# vca2.net
KiCad netlist of a schematic drawn in EAGLE
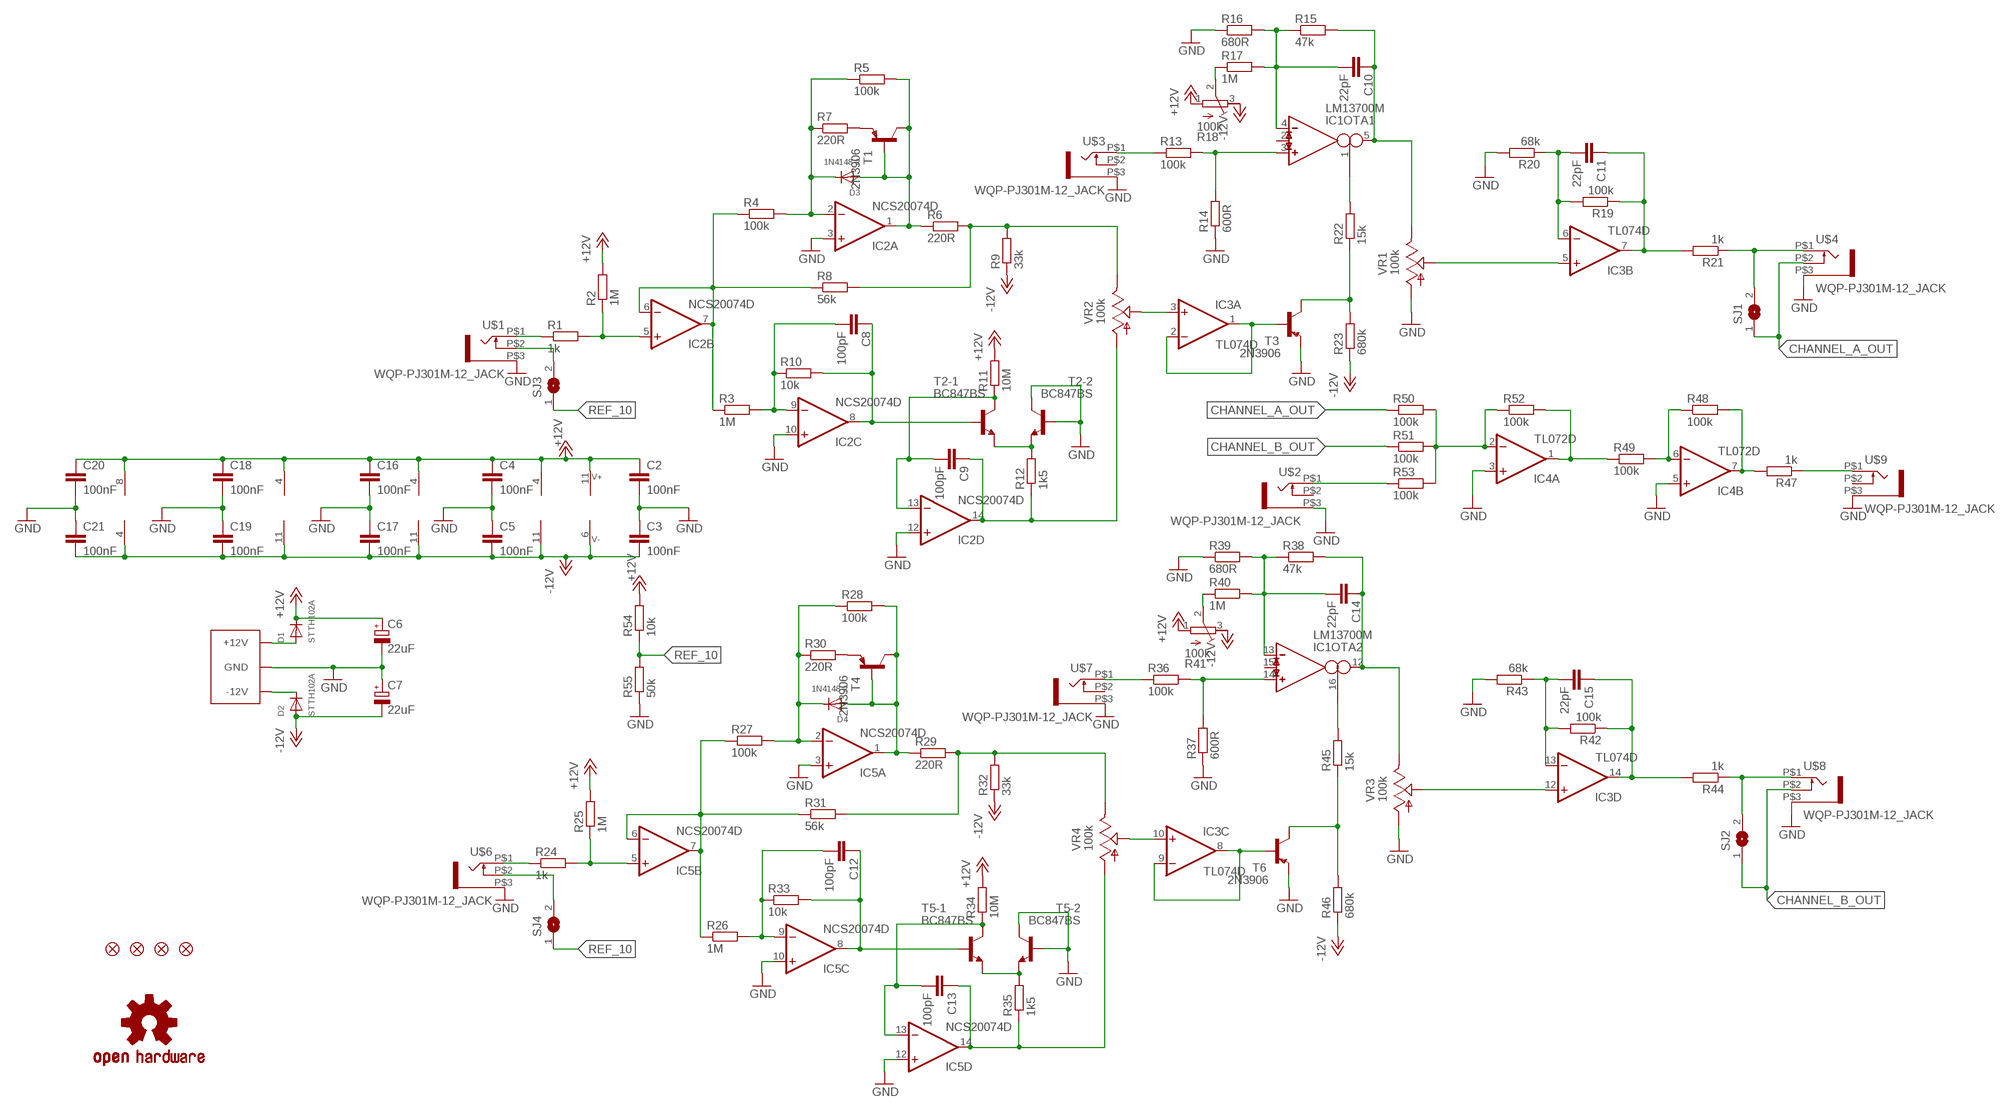
[diagram p0: schematic, sheet 1]

(export (version "E")
  (design (tool "Eeschema 10.0.6"))
  (components
    (comp (ref "C1")
      (value "EURO_POWER_LOCKFAT-LOCK")
      (footprint "eagle-import:EURO_PWR_HEADER_LOCK")
      (libsource (lib "eagle-import") (part "EURO_POWER_LOCKFAT-LOCK"))
    )
    (comp (ref "C2")
      (value "100nF")
      (footprint "eagle-import:C0603")
      (libsource (lib "eagle-import") (part "C-EUC0603"))
    )
    (comp (ref "C3")
      (value "100nF")
      (footprint "eagle-import:C0603")
      (libsource (lib "eagle-import") (part "C-EUC0603"))
    )
    (comp (ref "C4")
      (value "100nF")
      (footprint "eagle-import:C0603")
      (libsource (lib "eagle-import") (part "C-EUC0603"))
    )
    (comp (ref "C5")
      (value "100nF")
      (footprint "eagle-import:C0603")
      (libsource (lib "eagle-import") (part "C-EUC0603"))
    )
    (comp (ref "C6")
      (value "22uF")
      (footprint "eagle-import:PANASONIC_C")
      (libsource (lib "eagle-import") (part "CPOL-EUC"))
    )
    (comp (ref "C7")
      (value "22uF")
      (footprint "eagle-import:PANASONIC_C")
      (libsource (lib "eagle-import") (part "CPOL-EUC"))
    )
    (comp (ref "C8")
      (value "100pF")
      (footprint "eagle-import:C0603")
      (libsource (lib "eagle-import") (part "C-EUC0603"))
    )
    (comp (ref "C9")
      (value "100pF")
      (footprint "eagle-import:C0603")
      (libsource (lib "eagle-import") (part "C-EUC0603"))
    )
    (comp (ref "C10")
      (value "22pF")
      (footprint "eagle-import:C0603")
      (libsource (lib "eagle-import") (part "C-EUC0603"))
    )
    (comp (ref "C11")
      (value "22pF")
      (footprint "eagle-import:C0603")
      (libsource (lib "eagle-import") (part "C-EUC0603"))
    )
    (comp (ref "C12")
      (value "100pF")
      (footprint "eagle-import:C0603")
      (libsource (lib "eagle-import") (part "C-EUC0603"))
    )
    (comp (ref "C13")
      (value "100pF")
      (footprint "eagle-import:C0603")
      (libsource (lib "eagle-import") (part "C-EUC0603"))
    )
    (comp (ref "C14")
      (value "22pF")
      (footprint "eagle-import:C0603")
      (libsource (lib "eagle-import") (part "C-EUC0603"))
    )
    (comp (ref "C15")
      (value "22pF")
      (footprint "eagle-import:C0603")
      (libsource (lib "eagle-import") (part "C-EUC0603"))
    )
    (comp (ref "C16")
      (value "100nF")
      (footprint "eagle-import:C0603")
      (libsource (lib "eagle-import") (part "C-EUC0603"))
    )
    (comp (ref "C17")
      (value "100nF")
      (footprint "eagle-import:C0603")
      (libsource (lib "eagle-import") (part "C-EUC0603"))
    )
    (comp (ref "C18")
      (value "100nF")
      (footprint "eagle-import:C0603")
      (libsource (lib "eagle-import") (part "C-EUC0603"))
    )
    (comp (ref "C19")
      (value "100nF")
      (footprint "eagle-import:C0603")
      (libsource (lib "eagle-import") (part "C-EUC0603"))
    )
    (comp (ref "C20")
      (value "100nF")
      (footprint "eagle-import:C0603")
      (libsource (lib "eagle-import") (part "C-EUC0603"))
    )
    (comp (ref "C21")
      (value "100nF")
      (footprint "eagle-import:C0603")
      (libsource (lib "eagle-import") (part "C-EUC0603"))
    )
    (comp (ref "D1")
      (value "STTH102A")
      (footprint "eagle-import:SMADIODE")
      (libsource (lib "eagle-import") (part "DIODESMA"))
    )
    (comp (ref "D2")
      (value "STTH102A")
      (footprint "eagle-import:SMADIODE")
      (libsource (lib "eagle-import") (part "DIODESMA"))
    )
    (comp (ref "D3")
      (value "1N4148-2")
      (footprint "eagle-import:SOD-123")
      (libsource (lib "eagle-import") (part "DIODESOD-123"))
    )
    (comp (ref "D4")
      (value "1N4148-2")
      (footprint "eagle-import:SOD-123")
      (libsource (lib "eagle-import") (part "DIODESOD-123"))
    )
    (comp (ref "FD1")
      (value "FIDUCIAL1X2")
      (footprint "eagle-import:FIDUCIAL-1X2")
      (libsource (lib "eagle-import") (part "FIDUCIAL1X2"))
    )
    (comp (ref "FD2")
      (value "FIDUCIAL1X2")
      (footprint "eagle-import:FIDUCIAL-1X2")
      (libsource (lib "eagle-import") (part "FIDUCIAL1X2"))
    )
    (comp (ref "FD3")
      (value "FIDUCIAL1X2")
      (footprint "eagle-import:FIDUCIAL-1X2")
      (libsource (lib "eagle-import") (part "FIDUCIAL1X2"))
    )
    (comp (ref "FD4")
      (value "FIDUCIAL1X2")
      (footprint "eagle-import:FIDUCIAL-1X2")
      (libsource (lib "eagle-import") (part "FIDUCIAL1X2"))
    )
    (comp (ref "IC1")
      (value "LM13700M")
      (footprint "eagle-import:SO16")
      (libsource (lib "eagle-import") (part "LM13700M"))
    )
    (comp (ref "IC2")
      (value "NCS20074D")
      (footprint "eagle-import:SO14")
      (libsource (lib "eagle-import") (part "NCS20074D"))
    )
    (comp (ref "IC3")
      (value "TL074D")
      (footprint "eagle-import:SO14")
      (libsource (lib "eagle-import") (part "TL074D"))
    )
    (comp (ref "IC4")
      (value "TL072D")
      (footprint "eagle-import:SO08")
      (libsource (lib "eagle-import") (part "TL072D"))
    )
    (comp (ref "IC5")
      (value "NCS20074D")
      (footprint "eagle-import:SO14")
      (libsource (lib "eagle-import") (part "NCS20074D"))
    )
    (comp (ref "LOGO1")
      (value "OSHW-LOGOM")
      (footprint "eagle-import:OSHW-LOGO-M")
      (libsource (lib "eagle-import") (part "OSHW-LOGOM"))
    )
    (comp (ref "R1")
      (value "1k")
      (footprint "eagle-import:R0603")
      (libsource (lib "eagle-import") (part "R-EU_R0603"))
    )
    (comp (ref "R2")
      (value "1M")
      (footprint "eagle-import:R0603")
      (libsource (lib "eagle-import") (part "R-EU_R0603"))
    )
    (comp (ref "R3")
      (value "1M")
      (footprint "eagle-import:R0603")
      (libsource (lib "eagle-import") (part "R-EU_R0603"))
    )
    (comp (ref "R4")
      (value "100k")
      (footprint "eagle-import:R0603")
      (libsource (lib "eagle-import") (part "R-EU_R0603"))
    )
    (comp (ref "R5")
      (value "100k")
      (footprint "eagle-import:R0603")
      (libsource (lib "eagle-import") (part "R-EU_R0603"))
    )
    (comp (ref "R6")
      (value "220R")
      (footprint "eagle-import:R0603")
      (libsource (lib "eagle-import") (part "R-EU_R0603"))
    )
    (comp (ref "R7")
      (value "220R")
      (footprint "eagle-import:R0603")
      (libsource (lib "eagle-import") (part "R-EU_R0603"))
    )
    (comp (ref "R8")
      (value "56k")
      (footprint "eagle-import:R0603")
      (libsource (lib "eagle-import") (part "R-EU_R0603"))
    )
    (comp (ref "R9")
      (value "33k")
      (footprint "eagle-import:R0603")
      (libsource (lib "eagle-import") (part "R-EU_R0603"))
    )
    (comp (ref "R10")
      (value "10k")
      (footprint "eagle-import:R0603")
      (libsource (lib "eagle-import") (part "R-EU_R0603"))
    )
    (comp (ref "R11")
      (value "10M")
      (footprint "eagle-import:R0603")
      (libsource (lib "eagle-import") (part "R-EU_R0603"))
    )
    (comp (ref "R12")
      (value "1k5")
      (footprint "eagle-import:R0603")
      (libsource (lib "eagle-import") (part "R-EU_R0603"))
    )
    (comp (ref "R13")
      (value "100k")
      (footprint "eagle-import:R0603")
      (libsource (lib "eagle-import") (part "R-EU_R0603"))
    )
    (comp (ref "R14")
      (value "600R")
      (footprint "eagle-import:R0603")
      (libsource (lib "eagle-import") (part "R-EU_R0603"))
    )
    (comp (ref "R15")
      (value "47k")
      (footprint "eagle-import:R0603")
      (libsource (lib "eagle-import") (part "R-EU_R0603"))
    )
    (comp (ref "R16")
      (value "680R")
      (footprint "eagle-import:R0603")
      (libsource (lib "eagle-import") (part "R-EU_R0603"))
    )
    (comp (ref "R17")
      (value "1M")
      (footprint "eagle-import:R0603")
      (libsource (lib "eagle-import") (part "R-EU_R0603"))
    )
    (comp (ref "R18")
      (value "100k")
      (footprint "eagle-import:RTRIM64W")
      (libsource (lib "eagle-import") (part "R-TRIMM64W"))
    )
    (comp (ref "R19")
      (value "100k")
      (footprint "eagle-import:R0603")
      (libsource (lib "eagle-import") (part "R-EU_R0603"))
    )
    (comp (ref "R20")
      (value "68k")
      (footprint "eagle-import:R0603")
      (libsource (lib "eagle-import") (part "R-EU_R0603"))
    )
    (comp (ref "R21")
      (value "1k")
      (footprint "eagle-import:R0603")
      (libsource (lib "eagle-import") (part "R-EU_R0603"))
    )
    (comp (ref "R22")
      (value "15k")
      (footprint "eagle-import:R0603")
      (libsource (lib "eagle-import") (part "R-EU_R0603"))
    )
    (comp (ref "R23")
      (value "680k")
      (footprint "eagle-import:R0603")
      (libsource (lib "eagle-import") (part "R-EU_R0603"))
    )
    (comp (ref "R24")
      (value "1k")
      (footprint "eagle-import:R0603")
      (libsource (lib "eagle-import") (part "R-EU_R0603"))
    )
    (comp (ref "R25")
      (value "1M")
      (footprint "eagle-import:R0603")
      (libsource (lib "eagle-import") (part "R-EU_R0603"))
    )
    (comp (ref "R26")
      (value "1M")
      (footprint "eagle-import:R0603")
      (libsource (lib "eagle-import") (part "R-EU_R0603"))
    )
    (comp (ref "R27")
      (value "100k")
      (footprint "eagle-import:R0603")
      (libsource (lib "eagle-import") (part "R-EU_R0603"))
    )
    (comp (ref "R28")
      (value "100k")
      (footprint "eagle-import:R0603")
      (libsource (lib "eagle-import") (part "R-EU_R0603"))
    )
    (comp (ref "R29")
      (value "220R")
      (footprint "eagle-import:R0603")
      (libsource (lib "eagle-import") (part "R-EU_R0603"))
    )
    (comp (ref "R30")
      (value "220R")
      (footprint "eagle-import:R0603")
      (libsource (lib "eagle-import") (part "R-EU_R0603"))
    )
    (comp (ref "R31")
      (value "56k")
      (footprint "eagle-import:R0603")
      (libsource (lib "eagle-import") (part "R-EU_R0603"))
    )
    (comp (ref "R32")
      (value "33k")
      (footprint "eagle-import:R0603")
      (libsource (lib "eagle-import") (part "R-EU_R0603"))
    )
    (comp (ref "R33")
      (value "10k")
      (footprint "eagle-import:R0603")
      (libsource (lib "eagle-import") (part "R-EU_R0603"))
    )
    (comp (ref "R34")
      (value "10M")
      (footprint "eagle-import:R0603")
      (libsource (lib "eagle-import") (part "R-EU_R0603"))
    )
    (comp (ref "R35")
      (value "1k5")
      (footprint "eagle-import:R0603")
      (libsource (lib "eagle-import") (part "R-EU_R0603"))
    )
    (comp (ref "R36")
      (value "100k")
      (footprint "eagle-import:R0603")
      (libsource (lib "eagle-import") (part "R-EU_R0603"))
    )
    (comp (ref "R37")
      (value "600R")
      (footprint "eagle-import:R0603")
      (libsource (lib "eagle-import") (part "R-EU_R0603"))
    )
    (comp (ref "R38")
      (value "47k")
      (footprint "eagle-import:R0603")
      (libsource (lib "eagle-import") (part "R-EU_R0603"))
    )
    (comp (ref "R39")
      (value "680R")
      (footprint "eagle-import:R0603")
      (libsource (lib "eagle-import") (part "R-EU_R0603"))
    )
    (comp (ref "R40")
      (value "1M")
      (footprint "eagle-import:R0603")
      (libsource (lib "eagle-import") (part "R-EU_R0603"))
    )
    (comp (ref "R41")
      (value "100k")
      (footprint "eagle-import:RTRIM64W")
      (libsource (lib "eagle-import") (part "R-TRIMM64W"))
    )
    (comp (ref "R42")
      (value "100k")
      (footprint "eagle-import:R0603")
      (libsource (lib "eagle-import") (part "R-EU_R0603"))
    )
    (comp (ref "R43")
      (value "68k")
      (footprint "eagle-import:R0603")
      (libsource (lib "eagle-import") (part "R-EU_R0603"))
    )
    (comp (ref "R44")
      (value "1k")
      (footprint "eagle-import:R0603")
      (libsource (lib "eagle-import") (part "R-EU_R0603"))
    )
    (comp (ref "R45")
      (value "15k")
      (footprint "eagle-import:R0603")
      (libsource (lib "eagle-import") (part "R-EU_R0603"))
    )
    (comp (ref "R46")
      (value "680k")
      (footprint "eagle-import:R0603")
      (libsource (lib "eagle-import") (part "R-EU_R0603"))
    )
    (comp (ref "R47")
      (value "1k")
      (footprint "eagle-import:R0603")
      (libsource (lib "eagle-import") (part "R-EU_R0603"))
    )
    (comp (ref "R48")
      (value "100k")
      (footprint "eagle-import:R0603")
      (libsource (lib "eagle-import") (part "R-EU_R0603"))
    )
    (comp (ref "R49")
      (value "100k")
      (footprint "eagle-import:R0603")
      (libsource (lib "eagle-import") (part "R-EU_R0603"))
    )
    (comp (ref "R50")
      (value "100k")
      (footprint "eagle-import:R0603")
      (libsource (lib "eagle-import") (part "R-EU_R0603"))
    )
    (comp (ref "R51")
      (value "100k")
      (footprint "eagle-import:R0603")
      (libsource (lib "eagle-import") (part "R-EU_R0603"))
    )
    (comp (ref "R52")
      (value "100k")
      (footprint "eagle-import:R0603")
      (libsource (lib "eagle-import") (part "R-EU_R0603"))
    )
    (comp (ref "R53")
      (value "100k")
      (footprint "eagle-import:R0603")
      (libsource (lib "eagle-import") (part "R-EU_R0603"))
    )
    (comp (ref "R54")
      (value "10k")
      (footprint "eagle-import:R0603")
      (libsource (lib "eagle-import") (part "R-EU_R0603"))
    )
    (comp (ref "R55")
      (value "50k")
      (footprint "eagle-import:R0603")
      (libsource (lib "eagle-import") (part "R-EU_R0603"))
    )
    (comp (ref "SJ1") (value "SJ") (footprint "eagle-import:SJ") (libsource (lib "eagle-import") (part "SJ")))
    (comp (ref "SJ2") (value "SJ") (footprint "eagle-import:SJ") (libsource (lib "eagle-import") (part "SJ")))
    (comp (ref "SJ3") (value "SJ") (footprint "eagle-import:SJ") (libsource (lib "eagle-import") (part "SJ")))
    (comp (ref "SJ4") (value "SJ") (footprint "eagle-import:SJ") (libsource (lib "eagle-import") (part "SJ")))
    (comp (ref "T1")
      (value "2N3906")
      (footprint "eagle-import:SOT23-BEC")
      (libsource (lib "eagle-import") (part "-PNP-SOT23-BECMMBT3906LT1"))
    )
    (comp (ref "T2")
      (value "BC847BS")
      (footprint "eagle-import:SOT363")
      (libsource (lib "eagle-import") (part "BC847BS"))
    )
    (comp (ref "T3")
      (value "2N3906")
      (footprint "eagle-import:SOT23-BEC")
      (libsource (lib "eagle-import") (part "-PNP-SOT23-BECMMBT3906LT1"))
    )
    (comp (ref "T4")
      (value "2N3906")
      (footprint "eagle-import:SOT23-BEC")
      (libsource (lib "eagle-import") (part "-PNP-SOT23-BECMMBT3906LT1"))
    )
    (comp (ref "T5")
      (value "BC847BS")
      (footprint "eagle-import:SOT363")
      (libsource (lib "eagle-import") (part "BC847BS"))
    )
    (comp (ref "T6")
      (value "2N3906")
      (footprint "eagle-import:SOT23-BEC")
      (libsource (lib "eagle-import") (part "-PNP-SOT23-BECMMBT3906LT1"))
    )
    (comp (ref "U$1")
      (value "WQP-PJ301M-12_JACK")
      (footprint "eagle-import:WQP-PJ301M-12_JACK")
      (libsource (lib "eagle-import") (part "WQP-PJ301M-12_JACK"))
    )
    (comp (ref "U$2")
      (value "WQP-PJ301M-12_JACK")
      (footprint "eagle-import:WQP-PJ301M-12_JACK")
      (libsource (lib "eagle-import") (part "WQP-PJ301M-12_JACK"))
    )
    (comp (ref "U$3")
      (value "WQP-PJ301M-12_JACK")
      (footprint "eagle-import:WQP-PJ301M-12_JACK")
      (libsource (lib "eagle-import") (part "WQP-PJ301M-12_JACK"))
    )
    (comp (ref "U$4")
      (value "WQP-PJ301M-12_JACK")
      (footprint "eagle-import:WQP-PJ301M-12_JACK")
      (libsource (lib "eagle-import") (part "WQP-PJ301M-12_JACK"))
    )
    (comp (ref "U$6")
      (value "WQP-PJ301M-12_JACK")
      (footprint "eagle-import:WQP-PJ301M-12_JACK")
      (libsource (lib "eagle-import") (part "WQP-PJ301M-12_JACK"))
    )
    (comp (ref "U$7")
      (value "WQP-PJ301M-12_JACK")
      (footprint "eagle-import:WQP-PJ301M-12_JACK")
      (libsource (lib "eagle-import") (part "WQP-PJ301M-12_JACK"))
    )
    (comp (ref "U$8")
      (value "WQP-PJ301M-12_JACK")
      (footprint "eagle-import:WQP-PJ301M-12_JACK")
      (libsource (lib "eagle-import") (part "WQP-PJ301M-12_JACK"))
    )
    (comp (ref "U$9")
      (value "WQP-PJ301M-12_JACK")
      (footprint "eagle-import:WQP-PJ301M-12_JACK")
      (libsource (lib "eagle-import") (part "WQP-PJ301M-12_JACK"))
    )
    (comp (ref "VR1")
      (value "100k")
      (footprint "eagle-import:9MM_SNAP-IN_POT")
      (libsource (lib "eagle-import") (part "9MM_SNAP-IN_POT_"))
    )
    (comp (ref "VR2")
      (value "100k")
      (footprint "eagle-import:9MM_SNAP-IN_POT")
      (libsource (lib "eagle-import") (part "9MM_SNAP-IN_POT_"))
    )
    (comp (ref "VR3")
      (value "100k")
      (footprint "eagle-import:9MM_SNAP-IN_POT")
      (libsource (lib "eagle-import") (part "9MM_SNAP-IN_POT_"))
    )
    (comp (ref "VR4")
      (value "100k")
      (footprint "eagle-import:9MM_SNAP-IN_POT")
      (libsource (lib "eagle-import") (part "9MM_SNAP-IN_POT_"))
    )
  )
  (nets
    (net (code "1") (name "+12V") (class "Default")
      (node (ref "C16") (pin "1") (pinfunction "1_1") (pintype "passive"))
      (node (ref "C18") (pin "1") (pinfunction "1_1") (pintype "passive"))
      (node (ref "C2") (pin "1") (pinfunction "1_1") (pintype "passive"))
      (node (ref "C20") (pin "1") (pinfunction "1_1") (pintype "passive"))
      (node (ref "C4") (pin "1") (pinfunction "1_1") (pintype "passive"))
      (node (ref "C6") (pin "+") (pinfunction "+_+") (pintype "passive"))
      (node (ref "D1") (pin "C") (pinfunction "C_C") (pintype "passive"))
      (node (ref "IC1") (pin "11") (pinfunction "V+_11") (pintype "power_in"))
      (node (ref "IC2") (pin "4") (pinfunction "V+_4") (pintype "power_in"))
      (node (ref "IC3") (pin "4") (pinfunction "V+_4") (pintype "power_in"))
      (node (ref "IC4") (pin "8") (pinfunction "V+_8") (pintype "power_in"))
      (node (ref "IC5") (pin "4") (pinfunction "V+_4") (pintype "power_in"))
      (node (ref "R11") (pin "2") (pinfunction "2_2") (pintype "passive"))
      (node (ref "R18") (pin "1") (pinfunction "A_1") (pintype "passive"))
      (node (ref "R2") (pin "2") (pinfunction "2_2") (pintype "passive"))
      (node (ref "R25") (pin "2") (pinfunction "2_2") (pintype "passive"))
      (node (ref "R34") (pin "2") (pinfunction "2_2") (pintype "passive"))
      (node (ref "R41") (pin "1") (pinfunction "A_1") (pintype "passive"))
      (node (ref "R54") (pin "2") (pinfunction "2_2") (pintype "passive"))
    )
    (net (code "2") (name "-12V") (class "Default")
      (node (ref "C17") (pin "2") (pinfunction "2_2") (pintype "passive"))
      (node (ref "C19") (pin "2") (pinfunction "2_2") (pintype "passive"))
      (node (ref "C21") (pin "2") (pinfunction "2_2") (pintype "passive"))
      (node (ref "C3") (pin "2") (pinfunction "2_2") (pintype "passive"))
      (node (ref "C5") (pin "2") (pinfunction "2_2") (pintype "passive"))
      (node (ref "C7") (pin "-") (pinfunction "-_-") (pintype "passive"))
      (node (ref "D2") (pin "A") (pinfunction "A_A") (pintype "passive"))
      (node (ref "IC1") (pin "6") (pinfunction "V-_6") (pintype "power_in"))
      (node (ref "IC2") (pin "11") (pinfunction "V-_11") (pintype "power_in"))
      (node (ref "IC3") (pin "11") (pinfunction "V-_11") (pintype "power_in"))
      (node (ref "IC4") (pin "4") (pinfunction "V-_4") (pintype "power_in"))
      (node (ref "IC5") (pin "11") (pinfunction "V-_11") (pintype "power_in"))
      (node (ref "R18") (pin "3") (pinfunction "E_3") (pintype "passive"))
      (node (ref "R23") (pin "1") (pinfunction "1_1") (pintype "passive"))
      (node (ref "R32") (pin "1") (pinfunction "1_1") (pintype "passive"))
      (node (ref "R41") (pin "3") (pinfunction "E_3") (pintype "passive"))
      (node (ref "R46") (pin "1") (pinfunction "1_1") (pintype "passive"))
      (node (ref "R9") (pin "1") (pinfunction "1_1") (pintype "passive"))
    )
    (net (code "3") (name "CHANNEL_A_OUT") (class "Default")
      (node (ref "R50") (pin "1") (pinfunction "1_1") (pintype "passive"))
      (node (ref "SJ1") (pin "1") (pinfunction "1_1") (pintype "passive"))
      (node (ref "U$4") (pin "P$2") (pinfunction "3_P$2") (pintype "passive"))
    )
    (net (code "4") (name "CHANNEL_B_OUT") (class "Default")
      (node (ref "R51") (pin "1") (pinfunction "1_1") (pintype "passive"))
      (node (ref "SJ2") (pin "1") (pinfunction "1_1") (pintype "passive"))
      (node (ref "U$8") (pin "P$2") (pinfunction "3_P$2") (pintype "passive"))
    )
    (net (code "5") (name "GND") (class "Default")
      (node (ref "C1") (pin "GND1") (pinfunction "GND_GND1") (pintype "bidirectional"))
      (node (ref "C1") (pin "GND2") (pinfunction "GND_GND2") (pintype "bidirectional"))
      (node (ref "C1") (pin "GND3") (pinfunction "GND_GND3") (pintype "bidirectional"))
      (node (ref "C1") (pin "GND4") (pinfunction "GND_GND4") (pintype "bidirectional"))
      (node (ref "C1") (pin "GND5") (pinfunction "GND_GND5") (pintype "bidirectional"))
      (node (ref "C1") (pin "GND6") (pinfunction "GND_GND6") (pintype "bidirectional"))
      (node (ref "C16") (pin "2") (pinfunction "2_2") (pintype "passive"))
      (node (ref "C17") (pin "1") (pinfunction "1_1") (pintype "passive"))
      (node (ref "C18") (pin "2") (pinfunction "2_2") (pintype "passive"))
      (node (ref "C19") (pin "1") (pinfunction "1_1") (pintype "passive"))
      (node (ref "C2") (pin "2") (pinfunction "2_2") (pintype "passive"))
      (node (ref "C20") (pin "2") (pinfunction "2_2") (pintype "passive"))
      (node (ref "C21") (pin "1") (pinfunction "1_1") (pintype "passive"))
      (node (ref "C3") (pin "1") (pinfunction "1_1") (pintype "passive"))
      (node (ref "C4") (pin "2") (pinfunction "2_2") (pintype "passive"))
      (node (ref "C5") (pin "1") (pinfunction "1_1") (pintype "passive"))
      (node (ref "C6") (pin "-") (pinfunction "-_-") (pintype "passive"))
      (node (ref "C7") (pin "+") (pinfunction "+_+") (pintype "passive"))
      (node (ref "IC2") (pin "10") (pinfunction "+IN_10") (pintype "input"))
      (node (ref "IC2") (pin "12") (pinfunction "+IN_12") (pintype "input"))
      (node (ref "IC2") (pin "3") (pinfunction "+IN_3") (pintype "input"))
      (node (ref "IC4") (pin "3") (pinfunction "+IN_3") (pintype "input"))
      (node (ref "IC4") (pin "5") (pinfunction "+IN_5") (pintype "input"))
      (node (ref "IC5") (pin "10") (pinfunction "+IN_10") (pintype "input"))
      (node (ref "IC5") (pin "12") (pinfunction "+IN_12") (pintype "input"))
      (node (ref "IC5") (pin "3") (pinfunction "+IN_3") (pintype "input"))
      (node (ref "R14") (pin "1") (pinfunction "1_1") (pintype "passive"))
      (node (ref "R16") (pin "1") (pinfunction "1_1") (pintype "passive"))
      (node (ref "R20") (pin "2") (pinfunction "2_2") (pintype "passive"))
      (node (ref "R37") (pin "1") (pinfunction "1_1") (pintype "passive"))
      (node (ref "R39") (pin "1") (pinfunction "1_1") (pintype "passive"))
      (node (ref "R43") (pin "2") (pinfunction "2_2") (pintype "passive"))
      (node (ref "R55") (pin "1") (pinfunction "1_1") (pintype "passive"))
      (node (ref "T2") (pin "3") (pinfunction "C_3") (pintype "passive"))
      (node (ref "T2") (pin "5") (pinfunction "B_5") (pintype "passive"))
      (node (ref "T3") (pin "E") (pinfunction "E_E") (pintype "passive"))
      (node (ref "T5") (pin "3") (pinfunction "C_3") (pintype "passive"))
      (node (ref "T5") (pin "5") (pinfunction "B_5") (pintype "passive"))
      (node (ref "T6") (pin "E") (pinfunction "E_E") (pintype "passive"))
      (node (ref "U$1") (pin "P$3") (pinfunction "1_P$3") (pintype "passive"))
      (node (ref "U$2") (pin "P$3") (pinfunction "1_P$3") (pintype "passive"))
      (node (ref "U$3") (pin "P$3") (pinfunction "1_P$3") (pintype "passive"))
      (node (ref "U$4") (pin "P$3") (pinfunction "1_P$3") (pintype "passive"))
      (node (ref "U$6") (pin "P$3") (pinfunction "1_P$3") (pintype "passive"))
      (node (ref "U$7") (pin "P$3") (pinfunction "1_P$3") (pintype "passive"))
      (node (ref "U$8") (pin "P$3") (pinfunction "1_P$3") (pintype "passive"))
      (node (ref "U$9") (pin "P$3") (pinfunction "1_P$3") (pintype "passive"))
      (node (ref "VR1") (pin "1") (pinfunction "A_1") (pintype "passive"))
      (node (ref "VR3") (pin "1") (pinfunction "A_1") (pintype "passive"))
    )
    (net (code "6") (name "Net-(C1-+12V-PadPOS1)") (class "Default")
      (node (ref "C1") (pin "POS1") (pinfunction "+12V_POS1") (pintype "bidirectional"))
      (node (ref "C1") (pin "POS2") (pinfunction "+12V_POS2") (pintype "bidirectional"))
      (node (ref "D1") (pin "A") (pinfunction "A_A") (pintype "passive"))
    )
    (net (code "7") (name "Net-(C1--12V-PadNEG1)") (class "Default")
      (node (ref "C1") (pin "NEG1") (pinfunction "-12V_NEG1") (pintype "bidirectional"))
      (node (ref "C1") (pin "NEG2") (pinfunction "-12V_NEG2") (pintype "bidirectional"))
      (node (ref "D2") (pin "C") (pinfunction "C_C") (pintype "passive"))
    )
    (net (code "8") (name "Net-(IC1C-IN_N)") (class "Default")
      (node (ref "C10") (pin "2") (pinfunction "2_2") (pintype "passive"))
      (node (ref "IC1") (pin "4") (pinfunction "IN_N_4") (pintype "input"))
      (node (ref "R15") (pin "1") (pinfunction "1_1") (pintype "passive"))
      (node (ref "R16") (pin "2") (pinfunction "2_2") (pintype "passive"))
      (node (ref "R17") (pin "2") (pinfunction "2_2") (pintype "passive"))
    )
    (net (code "9") (name "Net-(IC1C-IN_P)") (class "Default")
      (node (ref "IC1") (pin "3") (pinfunction "IN_P_3") (pintype "input"))
      (node (ref "R13") (pin "2") (pinfunction "2_2") (pintype "passive"))
      (node (ref "R14") (pin "2") (pinfunction "2_2") (pintype "passive"))
    )
    (net (code "10") (name "Net-(IC1C-I_BIAS)") (class "Default")
      (node (ref "IC1") (pin "1") (pinfunction "I_BIAS_1") (pintype "input"))
      (node (ref "R22") (pin "2") (pinfunction "2_2") (pintype "passive"))
    )
    (net (code "11") (name "Net-(IC1C-OUT)") (class "Default")
      (node (ref "C10") (pin "1") (pinfunction "1_1") (pintype "passive"))
      (node (ref "IC1") (pin "5") (pinfunction "OUT_5") (pintype "output"))
      (node (ref "R15") (pin "2") (pinfunction "2_2") (pintype "passive"))
      (node (ref "VR1") (pin "3") (pinfunction "E_3") (pintype "passive"))
    )
    (net (code "12") (name "Net-(IC1D-IN_N)") (class "Default")
      (node (ref "C14") (pin "2") (pinfunction "2_2") (pintype "passive"))
      (node (ref "IC1") (pin "13") (pinfunction "IN_N_13") (pintype "input"))
      (node (ref "R38") (pin "1") (pinfunction "1_1") (pintype "passive"))
      (node (ref "R39") (pin "2") (pinfunction "2_2") (pintype "passive"))
      (node (ref "R40") (pin "2") (pinfunction "2_2") (pintype "passive"))
    )
    (net (code "13") (name "Net-(IC1D-IN_P)") (class "Default")
      (node (ref "IC1") (pin "14") (pinfunction "IN_P_14") (pintype "input"))
      (node (ref "R36") (pin "2") (pinfunction "2_2") (pintype "passive"))
      (node (ref "R37") (pin "2") (pinfunction "2_2") (pintype "passive"))
    )
    (net (code "14") (name "Net-(IC1D-I_BIAS)") (class "Default")
      (node (ref "IC1") (pin "16") (pinfunction "I_BIAS_16") (pintype "input"))
      (node (ref "R45") (pin "2") (pinfunction "2_2") (pintype "passive"))
    )
    (net (code "15") (name "Net-(IC1D-OUT)") (class "Default")
      (node (ref "C14") (pin "1") (pinfunction "1_1") (pintype "passive"))
      (node (ref "IC1") (pin "12") (pinfunction "OUT_12") (pintype "output"))
      (node (ref "R38") (pin "2") (pinfunction "2_2") (pintype "passive"))
      (node (ref "VR3") (pin "3") (pinfunction "E_3") (pintype "passive"))
    )
    (net (code "16") (name "Net-(IC2A--IN)") (class "Default")
      (node (ref "D3") (pin "C") (pinfunction "C_C") (pintype "passive"))
      (node (ref "IC2") (pin "2") (pinfunction "-IN_2") (pintype "input"))
      (node (ref "R4") (pin "2") (pinfunction "2_2") (pintype "passive"))
      (node (ref "R5") (pin "1") (pinfunction "1_1") (pintype "passive"))
      (node (ref "R7") (pin "1") (pinfunction "1_1") (pintype "passive"))
    )
    (net (code "17") (name "Net-(IC2A-OUT)") (class "Default")
      (node (ref "D3") (pin "A") (pinfunction "A_A") (pintype "passive"))
      (node (ref "IC2") (pin "1") (pinfunction "OUT_1") (pintype "output"))
      (node (ref "R5") (pin "2") (pinfunction "2_2") (pintype "passive"))
      (node (ref "R6") (pin "1") (pinfunction "1_1") (pintype "passive"))
      (node (ref "T1") (pin "B") (pinfunction "B_B") (pintype "passive"))
      (node (ref "T1") (pin "C") (pinfunction "C_C") (pintype "passive"))
    )
    (net (code "18") (name "Net-(IC2B-+IN)") (class "Default")
      (node (ref "IC2") (pin "5") (pinfunction "+IN_5") (pintype "input"))
      (node (ref "R1") (pin "2") (pinfunction "2_2") (pintype "passive"))
      (node (ref "R2") (pin "1") (pinfunction "1_1") (pintype "passive"))
    )
    (net (code "19") (name "Net-(IC2B--IN)") (class "Default")
      (node (ref "IC2") (pin "6") (pinfunction "-IN_6") (pintype "input"))
      (node (ref "IC2") (pin "7") (pinfunction "OUT_7") (pintype "output"))
      (node (ref "R3") (pin "1") (pinfunction "1_1") (pintype "passive"))
      (node (ref "R4") (pin "1") (pinfunction "1_1") (pintype "passive"))
      (node (ref "R8") (pin "1") (pinfunction "1_1") (pintype "passive"))
    )
    (net (code "20") (name "Net-(IC2C--IN)") (class "Default")
      (node (ref "C8") (pin "2") (pinfunction "2_2") (pintype "passive"))
      (node (ref "IC2") (pin "9") (pinfunction "-IN_9") (pintype "input"))
      (node (ref "R10") (pin "1") (pinfunction "1_1") (pintype "passive"))
      (node (ref "R3") (pin "2") (pinfunction "2_2") (pintype "passive"))
    )
    (net (code "21") (name "Net-(IC2C-OUT)") (class "Default")
      (node (ref "C8") (pin "1") (pinfunction "1_1") (pintype "passive"))
      (node (ref "IC2") (pin "8") (pinfunction "OUT_8") (pintype "output"))
      (node (ref "R10") (pin "2") (pinfunction "2_2") (pintype "passive"))
      (node (ref "T2") (pin "2") (pinfunction "B_2") (pintype "passive"))
    )
    (net (code "22") (name "Net-(IC2D--IN)") (class "Default")
      (node (ref "C9") (pin "2") (pinfunction "2_2") (pintype "passive"))
      (node (ref "IC2") (pin "13") (pinfunction "-IN_13") (pintype "input"))
      (node (ref "R11") (pin "1") (pinfunction "1_1") (pintype "passive"))
      (node (ref "T2") (pin "6") (pinfunction "C_6") (pintype "passive"))
    )
    (net (code "23") (name "Net-(IC2D-OUT)") (class "Default")
      (node (ref "C9") (pin "1") (pinfunction "1_1") (pintype "passive"))
      (node (ref "IC2") (pin "14") (pinfunction "OUT_14") (pintype "output"))
      (node (ref "R12") (pin "1") (pinfunction "1_1") (pintype "passive"))
      (node (ref "VR2") (pin "1") (pinfunction "A_1") (pintype "passive"))
    )
    (net (code "24") (name "Net-(IC3A-+IN)") (class "Default")
      (node (ref "IC3") (pin "3") (pinfunction "+IN_3") (pintype "input"))
      (node (ref "VR2") (pin "2") (pinfunction "S_2") (pintype "passive"))
    )
    (net (code "25") (name "Net-(IC3A--IN)") (class "Default")
      (node (ref "IC3") (pin "1") (pinfunction "OUT_1") (pintype "output"))
      (node (ref "IC3") (pin "2") (pinfunction "-IN_2") (pintype "input"))
      (node (ref "T3") (pin "B") (pinfunction "B_B") (pintype "passive"))
    )
    (net (code "26") (name "Net-(IC3B-+IN)") (class "Default")
      (node (ref "IC3") (pin "5") (pinfunction "+IN_5") (pintype "input"))
      (node (ref "VR1") (pin "2") (pinfunction "S_2") (pintype "passive"))
    )
    (net (code "27") (name "Net-(IC3B--IN)") (class "Default")
      (node (ref "C11") (pin "2") (pinfunction "2_2") (pintype "passive"))
      (node (ref "IC3") (pin "6") (pinfunction "-IN_6") (pintype "input"))
      (node (ref "R19") (pin "2") (pinfunction "2_2") (pintype "passive"))
      (node (ref "R20") (pin "1") (pinfunction "1_1") (pintype "passive"))
    )
    (net (code "28") (name "Net-(IC3B-OUT)") (class "Default")
      (node (ref "C11") (pin "1") (pinfunction "1_1") (pintype "passive"))
      (node (ref "IC3") (pin "7") (pinfunction "OUT_7") (pintype "output"))
      (node (ref "R19") (pin "1") (pinfunction "1_1") (pintype "passive"))
      (node (ref "R21") (pin "2") (pinfunction "2_2") (pintype "passive"))
    )
    (net (code "29") (name "Net-(IC3C-+IN)") (class "Default")
      (node (ref "IC3") (pin "10") (pinfunction "+IN_10") (pintype "input"))
      (node (ref "VR4") (pin "2") (pinfunction "S_2") (pintype "passive"))
    )
    (net (code "30") (name "Net-(IC3C--IN)") (class "Default")
      (node (ref "IC3") (pin "8") (pinfunction "OUT_8") (pintype "output"))
      (node (ref "IC3") (pin "9") (pinfunction "-IN_9") (pintype "input"))
      (node (ref "T6") (pin "B") (pinfunction "B_B") (pintype "passive"))
    )
    (net (code "31") (name "Net-(IC3D-+IN)") (class "Default")
      (node (ref "IC3") (pin "12") (pinfunction "+IN_12") (pintype "input"))
      (node (ref "VR3") (pin "2") (pinfunction "S_2") (pintype "passive"))
    )
    (net (code "32") (name "Net-(IC3D--IN)") (class "Default")
      (node (ref "C15") (pin "2") (pinfunction "2_2") (pintype "passive"))
      (node (ref "IC3") (pin "13") (pinfunction "-IN_13") (pintype "input"))
      (node (ref "R42") (pin "2") (pinfunction "2_2") (pintype "passive"))
      (node (ref "R43") (pin "1") (pinfunction "1_1") (pintype "passive"))
    )
    (net (code "33") (name "Net-(IC3D-OUT)") (class "Default")
      (node (ref "C15") (pin "1") (pinfunction "1_1") (pintype "passive"))
      (node (ref "IC3") (pin "14") (pinfunction "OUT_14") (pintype "output"))
      (node (ref "R42") (pin "1") (pinfunction "1_1") (pintype "passive"))
      (node (ref "R44") (pin "2") (pinfunction "2_2") (pintype "passive"))
    )
    (net (code "34") (name "Net-(IC4A--IN)") (class "Default")
      (node (ref "IC4") (pin "2") (pinfunction "-IN_2") (pintype "input"))
      (node (ref "R50") (pin "2") (pinfunction "2_2") (pintype "passive"))
      (node (ref "R51") (pin "2") (pinfunction "2_2") (pintype "passive"))
      (node (ref "R52") (pin "1") (pinfunction "1_1") (pintype "passive"))
      (node (ref "R53") (pin "2") (pinfunction "2_2") (pintype "passive"))
    )
    (net (code "35") (name "Net-(IC4A-OUT)") (class "Default")
      (node (ref "IC4") (pin "1") (pinfunction "OUT_1") (pintype "output"))
      (node (ref "R49") (pin "1") (pinfunction "1_1") (pintype "passive"))
      (node (ref "R52") (pin "2") (pinfunction "2_2") (pintype "passive"))
    )
    (net (code "36") (name "Net-(IC4B--IN)") (class "Default")
      (node (ref "IC4") (pin "6") (pinfunction "-IN_6") (pintype "input"))
      (node (ref "R48") (pin "1") (pinfunction "1_1") (pintype "passive"))
      (node (ref "R49") (pin "2") (pinfunction "2_2") (pintype "passive"))
    )
    (net (code "37") (name "Net-(IC4B-OUT)") (class "Default")
      (node (ref "IC4") (pin "7") (pinfunction "OUT_7") (pintype "output"))
      (node (ref "R47") (pin "2") (pinfunction "2_2") (pintype "passive"))
      (node (ref "R48") (pin "2") (pinfunction "2_2") (pintype "passive"))
    )
    (net (code "38") (name "Net-(IC5A--IN)") (class "Default")
      (node (ref "D4") (pin "C") (pinfunction "C_C") (pintype "passive"))
      (node (ref "IC5") (pin "2") (pinfunction "-IN_2") (pintype "input"))
      (node (ref "R27") (pin "2") (pinfunction "2_2") (pintype "passive"))
      (node (ref "R28") (pin "1") (pinfunction "1_1") (pintype "passive"))
      (node (ref "R30") (pin "1") (pinfunction "1_1") (pintype "passive"))
    )
    (net (code "39") (name "Net-(IC5A-OUT)") (class "Default")
      (node (ref "D4") (pin "A") (pinfunction "A_A") (pintype "passive"))
      (node (ref "IC5") (pin "1") (pinfunction "OUT_1") (pintype "output"))
      (node (ref "R28") (pin "2") (pinfunction "2_2") (pintype "passive"))
      (node (ref "R29") (pin "1") (pinfunction "1_1") (pintype "passive"))
      (node (ref "T4") (pin "B") (pinfunction "B_B") (pintype "passive"))
      (node (ref "T4") (pin "C") (pinfunction "C_C") (pintype "passive"))
    )
    (net (code "40") (name "Net-(IC5B-+IN)") (class "Default")
      (node (ref "IC5") (pin "5") (pinfunction "+IN_5") (pintype "input"))
      (node (ref "R24") (pin "2") (pinfunction "2_2") (pintype "passive"))
      (node (ref "R25") (pin "1") (pinfunction "1_1") (pintype "passive"))
    )
    (net (code "41") (name "Net-(IC5B--IN)") (class "Default")
      (node (ref "IC5") (pin "6") (pinfunction "-IN_6") (pintype "input"))
      (node (ref "IC5") (pin "7") (pinfunction "OUT_7") (pintype "output"))
      (node (ref "R26") (pin "1") (pinfunction "1_1") (pintype "passive"))
      (node (ref "R27") (pin "1") (pinfunction "1_1") (pintype "passive"))
      (node (ref "R31") (pin "1") (pinfunction "1_1") (pintype "passive"))
    )
    (net (code "42") (name "Net-(IC5C--IN)") (class "Default")
      (node (ref "C12") (pin "2") (pinfunction "2_2") (pintype "passive"))
      (node (ref "IC5") (pin "9") (pinfunction "-IN_9") (pintype "input"))
      (node (ref "R26") (pin "2") (pinfunction "2_2") (pintype "passive"))
      (node (ref "R33") (pin "1") (pinfunction "1_1") (pintype "passive"))
    )
    (net (code "43") (name "Net-(IC5C-OUT)") (class "Default")
      (node (ref "C12") (pin "1") (pinfunction "1_1") (pintype "passive"))
      (node (ref "IC5") (pin "8") (pinfunction "OUT_8") (pintype "output"))
      (node (ref "R33") (pin "2") (pinfunction "2_2") (pintype "passive"))
      (node (ref "T5") (pin "2") (pinfunction "B_2") (pintype "passive"))
    )
    (net (code "44") (name "Net-(IC5D--IN)") (class "Default")
      (node (ref "C13") (pin "2") (pinfunction "2_2") (pintype "passive"))
      (node (ref "IC5") (pin "13") (pinfunction "-IN_13") (pintype "input"))
      (node (ref "R34") (pin "1") (pinfunction "1_1") (pintype "passive"))
      (node (ref "T5") (pin "6") (pinfunction "C_6") (pintype "passive"))
    )
    (net (code "45") (name "Net-(IC5D-OUT)") (class "Default")
      (node (ref "C13") (pin "1") (pinfunction "1_1") (pintype "passive"))
      (node (ref "IC5") (pin "14") (pinfunction "OUT_14") (pintype "output"))
      (node (ref "R35") (pin "1") (pinfunction "1_1") (pintype "passive"))
      (node (ref "VR4") (pin "1") (pinfunction "A_1") (pintype "passive"))
    )
    (net (code "46") (name "Net-(R7-Pad2)") (class "Default")
      (node (ref "R7") (pin "2") (pinfunction "2_2") (pintype "passive"))
      (node (ref "T1") (pin "E") (pinfunction "E_E") (pintype "passive"))
    )
    (net (code "47") (name "Net-(R18-S)") (class "Default")
      (node (ref "R17") (pin "1") (pinfunction "1_1") (pintype "passive"))
      (node (ref "R18") (pin "2") (pinfunction "S_2") (pintype "passive"))
    )
    (net (code "48") (name "Net-(R22-Pad1)") (class "Default")
      (node (ref "R22") (pin "1") (pinfunction "1_1") (pintype "passive"))
      (node (ref "R23") (pin "2") (pinfunction "2_2") (pintype "passive"))
      (node (ref "T3") (pin "C") (pinfunction "C_C") (pintype "passive"))
    )
    (net (code "49") (name "Net-(R30-Pad2)") (class "Default")
      (node (ref "R30") (pin "2") (pinfunction "2_2") (pintype "passive"))
      (node (ref "T4") (pin "E") (pinfunction "E_E") (pintype "passive"))
    )
    (net (code "50") (name "Net-(R41-S)") (class "Default")
      (node (ref "R40") (pin "1") (pinfunction "1_1") (pintype "passive"))
      (node (ref "R41") (pin "2") (pinfunction "S_2") (pintype "passive"))
    )
    (net (code "51") (name "Net-(R45-Pad1)") (class "Default")
      (node (ref "R45") (pin "1") (pinfunction "1_1") (pintype "passive"))
      (node (ref "R46") (pin "2") (pinfunction "2_2") (pintype "passive"))
      (node (ref "T6") (pin "C") (pinfunction "C_C") (pintype "passive"))
    )
    (net (code "52") (name "Net-(T2A-E)") (class "Default")
      (node (ref "R12") (pin "2") (pinfunction "2_2") (pintype "passive"))
      (node (ref "T2") (pin "1") (pinfunction "E_1") (pintype "passive"))
      (node (ref "T2") (pin "4") (pinfunction "E_4") (pintype "passive"))
    )
    (net (code "53") (name "Net-(T5A-E)") (class "Default")
      (node (ref "R35") (pin "2") (pinfunction "2_2") (pintype "passive"))
      (node (ref "T5") (pin "1") (pinfunction "E_1") (pintype "passive"))
      (node (ref "T5") (pin "4") (pinfunction "E_4") (pintype "passive"))
    )
    (net (code "54") (name "Net-(U$1-2)") (class "Default")
      (node (ref "R1") (pin "1") (pinfunction "1_1") (pintype "passive"))
      (node (ref "U$1") (pin "P$1") (pinfunction "2_P$1") (pintype "passive"))
    )
    (net (code "55") (name "Net-(U$1-3)") (class "Default")
      (node (ref "SJ3") (pin "2") (pinfunction "2_2") (pintype "passive"))
      (node (ref "U$1") (pin "P$2") (pinfunction "3_P$2") (pintype "passive"))
    )
    (net (code "56") (name "Net-(U$2-2)") (class "Default")
      (node (ref "R53") (pin "1") (pinfunction "1_1") (pintype "passive"))
      (node (ref "U$2") (pin "P$1") (pinfunction "2_P$1") (pintype "passive"))
    )
    (net (code "57") (name "Net-(U$3-2)") (class "Default")
      (node (ref "R13") (pin "1") (pinfunction "1_1") (pintype "passive"))
      (node (ref "U$3") (pin "P$1") (pinfunction "2_P$1") (pintype "passive"))
    )
    (net (code "58") (name "Net-(U$4-2)") (class "Default")
      (node (ref "R21") (pin "1") (pinfunction "1_1") (pintype "passive"))
      (node (ref "SJ1") (pin "2") (pinfunction "2_2") (pintype "passive"))
      (node (ref "U$4") (pin "P$1") (pinfunction "2_P$1") (pintype "passive"))
    )
    (net (code "59") (name "Net-(U$6-2)") (class "Default")
      (node (ref "R24") (pin "1") (pinfunction "1_1") (pintype "passive"))
      (node (ref "U$6") (pin "P$1") (pinfunction "2_P$1") (pintype "passive"))
    )
    (net (code "60") (name "Net-(U$6-3)") (class "Default")
      (node (ref "SJ4") (pin "2") (pinfunction "2_2") (pintype "passive"))
      (node (ref "U$6") (pin "P$2") (pinfunction "3_P$2") (pintype "passive"))
    )
    (net (code "61") (name "Net-(U$7-2)") (class "Default")
      (node (ref "R36") (pin "1") (pinfunction "1_1") (pintype "passive"))
      (node (ref "U$7") (pin "P$1") (pinfunction "2_P$1") (pintype "passive"))
    )
    (net (code "62") (name "Net-(U$8-2)") (class "Default")
      (node (ref "R44") (pin "1") (pinfunction "1_1") (pintype "passive"))
      (node (ref "SJ2") (pin "2") (pinfunction "2_2") (pintype "passive"))
      (node (ref "U$8") (pin "P$1") (pinfunction "2_P$1") (pintype "passive"))
    )
    (net (code "63") (name "Net-(U$9-2)") (class "Default")
      (node (ref "R47") (pin "1") (pinfunction "1_1") (pintype "passive"))
      (node (ref "U$9") (pin "P$1") (pinfunction "2_P$1") (pintype "passive"))
    )
    (net (code "64") (name "Net-(VR2-E)") (class "Default")
      (node (ref "R6") (pin "2") (pinfunction "2_2") (pintype "passive"))
      (node (ref "R8") (pin "2") (pinfunction "2_2") (pintype "passive"))
      (node (ref "R9") (pin "2") (pinfunction "2_2") (pintype "passive"))
      (node (ref "VR2") (pin "3") (pinfunction "E_3") (pintype "passive"))
    )
    (net (code "65") (name "Net-(VR4-E)") (class "Default")
      (node (ref "R29") (pin "2") (pinfunction "2_2") (pintype "passive"))
      (node (ref "R31") (pin "2") (pinfunction "2_2") (pintype "passive"))
      (node (ref "R32") (pin "2") (pinfunction "2_2") (pintype "passive"))
      (node (ref "VR4") (pin "3") (pinfunction "E_3") (pintype "passive"))
    )
    (net (code "66") (name "REF_10") (class "Default")
      (node (ref "R54") (pin "1") (pinfunction "1_1") (pintype "passive"))
      (node (ref "R55") (pin "2") (pinfunction "2_2") (pintype "passive"))
      (node (ref "SJ3") (pin "1") (pinfunction "1_1") (pintype "passive"))
      (node (ref "SJ4") (pin "1") (pinfunction "1_1") (pintype "passive"))
    )
    (net (code "67") (name "unconnected-(IC1C-I_DIODE-Pad2)") (class "Default")
      (node (ref "IC1") (pin "2") (pinfunction "I_DIODE_2") (pintype "input"))
    )
    (net (code "68") (name "unconnected-(IC1D-I_DIODE-Pad15)") (class "Default")
      (node (ref "IC1") (pin "15") (pinfunction "I_DIODE_15") (pintype "input"))
    )
    (net (code "69") (name "unconnected-(U$2-3-PadP$2)") (class "Default")
      (node (ref "U$2") (pin "P$2") (pinfunction "3_P$2") (pintype "passive"))
    )
    (net (code "70") (name "unconnected-(U$3-3-PadP$2)") (class "Default")
      (node (ref "U$3") (pin "P$2") (pinfunction "3_P$2") (pintype "passive"))
    )
    (net (code "71") (name "unconnected-(U$7-3-PadP$2)") (class "Default")
      (node (ref "U$7") (pin "P$2") (pinfunction "3_P$2") (pintype "passive"))
    )
    (net (code "72") (name "unconnected-(U$9-3-PadP$2)") (class "Default")
      (node (ref "U$9") (pin "P$2") (pinfunction "3_P$2") (pintype "passive"))
    )
  )
)
